# W520B.net
KiCad netlist of a schematic drawn in EAGLE
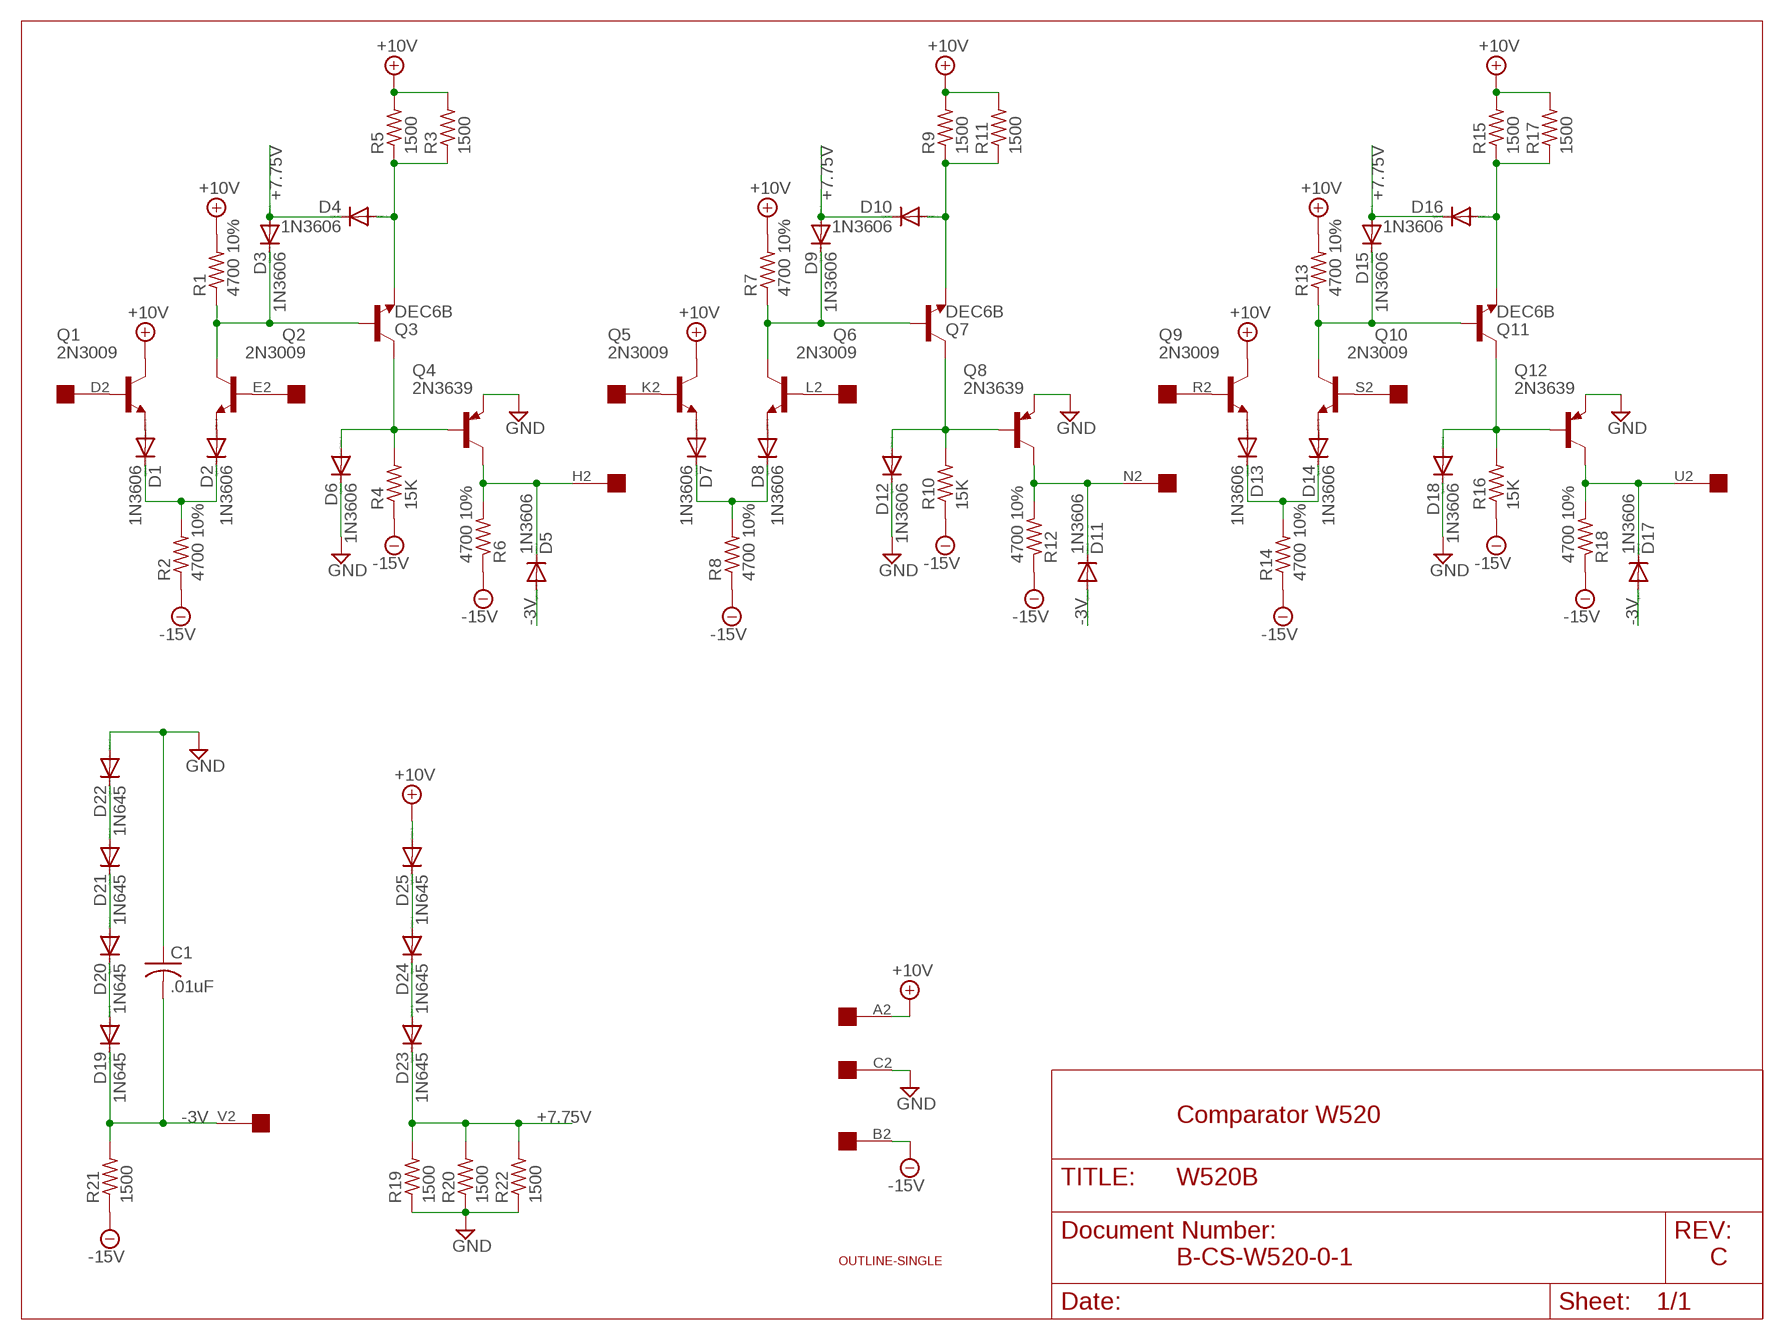
[diagram p0: schematic, sheet 1]

(export (version "E")
  (design (tool "Eeschema 10.0.6"))
  (components
    (comp (ref "C1")
      (value ".01uF")
      (footprint "eagle-import:C150-054X183")
      (libsource (lib "eagle-import") (part "C-US150-054X183"))
    )
    (comp (ref "D1")
      (value "1N3606")
      (footprint "eagle-import:DO35-10")
      (libsource (lib "eagle-import") (part "1N4148DO35-10"))
    )
    (comp (ref "D2")
      (value "1N3606")
      (footprint "eagle-import:DO35-10")
      (libsource (lib "eagle-import") (part "1N4148DO35-10"))
    )
    (comp (ref "D3")
      (value "1N3606")
      (footprint "eagle-import:DO35-10")
      (libsource (lib "eagle-import") (part "1N4148DO35-10"))
    )
    (comp (ref "D4")
      (value "1N3606")
      (footprint "eagle-import:DO35-10")
      (libsource (lib "eagle-import") (part "1N4148DO35-10"))
    )
    (comp (ref "D5")
      (value "1N3606")
      (footprint "eagle-import:DO35-10")
      (libsource (lib "eagle-import") (part "1N4148DO35-10"))
    )
    (comp (ref "D6")
      (value "1N3606")
      (footprint "eagle-import:DO35-10")
      (libsource (lib "eagle-import") (part "1N4148DO35-10"))
    )
    (comp (ref "D7")
      (value "1N3606")
      (footprint "eagle-import:DO35-10")
      (libsource (lib "eagle-import") (part "1N4148DO35-10"))
    )
    (comp (ref "D8")
      (value "1N3606")
      (footprint "eagle-import:DO35-10")
      (libsource (lib "eagle-import") (part "1N4148DO35-10"))
    )
    (comp (ref "D9")
      (value "1N3606")
      (footprint "eagle-import:DO35-10")
      (libsource (lib "eagle-import") (part "1N4148DO35-10"))
    )
    (comp (ref "D10")
      (value "1N3606")
      (footprint "eagle-import:DO35-10")
      (libsource (lib "eagle-import") (part "1N4148DO35-10"))
    )
    (comp (ref "D11")
      (value "1N3606")
      (footprint "eagle-import:DO35-10")
      (libsource (lib "eagle-import") (part "1N4148DO35-10"))
    )
    (comp (ref "D12")
      (value "1N3606")
      (footprint "eagle-import:DO35-10")
      (libsource (lib "eagle-import") (part "1N4148DO35-10"))
    )
    (comp (ref "D13")
      (value "1N3606")
      (footprint "eagle-import:DO35-10")
      (libsource (lib "eagle-import") (part "1N4148DO35-10"))
    )
    (comp (ref "D14")
      (value "1N3606")
      (footprint "eagle-import:DO35-10")
      (libsource (lib "eagle-import") (part "1N4148DO35-10"))
    )
    (comp (ref "D15")
      (value "1N3606")
      (footprint "eagle-import:DO35-10")
      (libsource (lib "eagle-import") (part "1N4148DO35-10"))
    )
    (comp (ref "D16")
      (value "1N3606")
      (footprint "eagle-import:DO35-10")
      (libsource (lib "eagle-import") (part "1N4148DO35-10"))
    )
    (comp (ref "D17")
      (value "1N3606")
      (footprint "eagle-import:DO35-10")
      (libsource (lib "eagle-import") (part "1N4148DO35-10"))
    )
    (comp (ref "D18")
      (value "1N3606")
      (footprint "eagle-import:DO35-10")
      (libsource (lib "eagle-import") (part "1N4148DO35-10"))
    )
    (comp (ref "D19")
      (value "1N645")
      (footprint "eagle-import:DO35-10")
      (libsource (lib "eagle-import") (part "1N4148DO35-10"))
    )
    (comp (ref "D20")
      (value "1N645")
      (footprint "eagle-import:DO35-10")
      (libsource (lib "eagle-import") (part "1N4148DO35-10"))
    )
    (comp (ref "D21")
      (value "1N645")
      (footprint "eagle-import:DO35-10")
      (libsource (lib "eagle-import") (part "1N4148DO35-10"))
    )
    (comp (ref "D22")
      (value "1N645")
      (footprint "eagle-import:DO35-10")
      (libsource (lib "eagle-import") (part "1N4148DO35-10"))
    )
    (comp (ref "D23")
      (value "1N645")
      (footprint "eagle-import:DO35-10")
      (libsource (lib "eagle-import") (part "1N4148DO35-10"))
    )
    (comp (ref "D24")
      (value "1N645")
      (footprint "eagle-import:DO35-10")
      (libsource (lib "eagle-import") (part "1N4148DO35-10"))
    )
    (comp (ref "D25")
      (value "1N645")
      (footprint "eagle-import:DO35-10")
      (libsource (lib "eagle-import") (part "1N4148DO35-10"))
    )
    (comp (ref "Q1")
      (value "2N3009")
      (footprint "eagle-import:TO5")
      (libsource (lib "eagle-import") (part "2N2102"))
    )
    (comp (ref "Q2")
      (value "2N3009")
      (footprint "eagle-import:TO5")
      (libsource (lib "eagle-import") (part "2N2102"))
    )
    (comp (ref "Q3")
      (value "DEC6B")
      (footprint "eagle-import:TO5")
      (libsource (lib "eagle-import") (part "2N2102"))
    )
    (comp (ref "Q4")
      (value "2N3639")
      (footprint "eagle-import:TO39")
      (libsource (lib "eagle-import") (part "2N2904"))
    )
    (comp (ref "Q5")
      (value "2N3009")
      (footprint "eagle-import:TO5")
      (libsource (lib "eagle-import") (part "2N2102"))
    )
    (comp (ref "Q6")
      (value "2N3009")
      (footprint "eagle-import:TO5")
      (libsource (lib "eagle-import") (part "2N2102"))
    )
    (comp (ref "Q7")
      (value "DEC6B")
      (footprint "eagle-import:TO5")
      (libsource (lib "eagle-import") (part "2N2102"))
    )
    (comp (ref "Q8")
      (value "2N3639")
      (footprint "eagle-import:TO39")
      (libsource (lib "eagle-import") (part "2N2904"))
    )
    (comp (ref "Q9")
      (value "2N3009")
      (footprint "eagle-import:TO5")
      (libsource (lib "eagle-import") (part "2N2102"))
    )
    (comp (ref "Q10")
      (value "2N3009")
      (footprint "eagle-import:TO5")
      (libsource (lib "eagle-import") (part "2N2102"))
    )
    (comp (ref "Q11")
      (value "DEC6B")
      (footprint "eagle-import:TO5")
      (libsource (lib "eagle-import") (part "2N2102"))
    )
    (comp (ref "Q12")
      (value "2N3639")
      (footprint "eagle-import:TO39")
      (libsource (lib "eagle-import") (part "2N2904"))
    )
    (comp (ref "R1")
      (value "4700 10%")
      (footprint "eagle-import:0207_10")
      (libsource (lib "eagle-import") (part "R-US_0207/10"))
    )
    (comp (ref "R2")
      (value "4700 10%")
      (footprint "eagle-import:0207_10")
      (libsource (lib "eagle-import") (part "R-US_0207/10"))
    )
    (comp (ref "R3")
      (value "1500")
      (footprint "eagle-import:0207_10")
      (libsource (lib "eagle-import") (part "R-US_0207/10"))
    )
    (comp (ref "R4")
      (value "15K")
      (footprint "eagle-import:0207_10")
      (libsource (lib "eagle-import") (part "R-US_0207/10"))
    )
    (comp (ref "R5")
      (value "1500")
      (footprint "eagle-import:0207_10")
      (libsource (lib "eagle-import") (part "R-US_0207/10"))
    )
    (comp (ref "R6")
      (value "4700 10%")
      (footprint "eagle-import:0207_10")
      (libsource (lib "eagle-import") (part "R-US_0207/10"))
    )
    (comp (ref "R7")
      (value "4700 10%")
      (footprint "eagle-import:0207_10")
      (libsource (lib "eagle-import") (part "R-US_0207/10"))
    )
    (comp (ref "R8")
      (value "4700 10%")
      (footprint "eagle-import:0207_10")
      (libsource (lib "eagle-import") (part "R-US_0207/10"))
    )
    (comp (ref "R9")
      (value "1500")
      (footprint "eagle-import:0207_10")
      (libsource (lib "eagle-import") (part "R-US_0207/10"))
    )
    (comp (ref "R10")
      (value "15K")
      (footprint "eagle-import:0207_10")
      (libsource (lib "eagle-import") (part "R-US_0207/10"))
    )
    (comp (ref "R11")
      (value "1500")
      (footprint "eagle-import:0207_10")
      (libsource (lib "eagle-import") (part "R-US_0207/10"))
    )
    (comp (ref "R12")
      (value "4700 10%")
      (footprint "eagle-import:0207_10")
      (libsource (lib "eagle-import") (part "R-US_0207/10"))
    )
    (comp (ref "R13")
      (value "4700 10%")
      (footprint "eagle-import:0207_10")
      (libsource (lib "eagle-import") (part "R-US_0207/10"))
    )
    (comp (ref "R14")
      (value "4700 10%")
      (footprint "eagle-import:0207_10")
      (libsource (lib "eagle-import") (part "R-US_0207/10"))
    )
    (comp (ref "R15")
      (value "1500")
      (footprint "eagle-import:0207_10")
      (libsource (lib "eagle-import") (part "R-US_0207/10"))
    )
    (comp (ref "R16")
      (value "15K")
      (footprint "eagle-import:0207_10")
      (libsource (lib "eagle-import") (part "R-US_0207/10"))
    )
    (comp (ref "R17")
      (value "1500")
      (footprint "eagle-import:0207_10")
      (libsource (lib "eagle-import") (part "R-US_0207/10"))
    )
    (comp (ref "R18")
      (value "4700 10%")
      (footprint "eagle-import:0207_10")
      (libsource (lib "eagle-import") (part "R-US_0207/10"))
    )
    (comp (ref "R19")
      (value "1500")
      (footprint "eagle-import:0207_10")
      (libsource (lib "eagle-import") (part "R-US_0207/10"))
    )
    (comp (ref "R20")
      (value "1500")
      (footprint "eagle-import:0207_10")
      (libsource (lib "eagle-import") (part "R-US_0207/10"))
    )
    (comp (ref "R21")
      (value "1500")
      (footprint "eagle-import:0207_10")
      (libsource (lib "eagle-import") (part "R-US_0207/10"))
    )
    (comp (ref "R22")
      (value "1500")
      (footprint "eagle-import:0207_10")
      (libsource (lib "eagle-import") (part "R-US_0207/10"))
    )
    (comp (ref "U$1")
      (value "OUTLINE-SINGLE")
      (footprint "eagle-import:SINGLE")
      (libsource (lib "eagle-import") (part "OUTLINE-SINGLE"))
    )
    (comp (ref "U$2")
      (value "EDGE-1")
      (footprint "eagle-import:EDGE-CON1")
      (libsource (lib "eagle-import") (part "EDGE-1"))
    )
  )
  (nets
    (net (code "1") (name "+10V") (class "Default")
      (node (ref "D25") (pin "A") (pinfunction "A_A") (pintype "passive"))
      (node (ref "Q1") (pin "3") (pinfunction "C_3") (pintype "passive"))
      (node (ref "Q5") (pin "3") (pinfunction "C_3") (pintype "passive"))
      (node (ref "Q9") (pin "3") (pinfunction "C_3") (pintype "passive"))
      (node (ref "R1") (pin "2") (pinfunction "2_2") (pintype "passive"))
      (node (ref "R11") (pin "2") (pinfunction "2_2") (pintype "passive"))
      (node (ref "R13") (pin "2") (pinfunction "2_2") (pintype "passive"))
      (node (ref "R15") (pin "2") (pinfunction "2_2") (pintype "passive"))
      (node (ref "R17") (pin "2") (pinfunction "2_2") (pintype "passive"))
      (node (ref "R3") (pin "2") (pinfunction "2_2") (pintype "passive"))
      (node (ref "R5") (pin "2") (pinfunction "2_2") (pintype "passive"))
      (node (ref "R7") (pin "2") (pinfunction "2_2") (pintype "passive"))
      (node (ref "R9") (pin "2") (pinfunction "2_2") (pintype "passive"))
      (node (ref "U$2") (pin "A2") (pinfunction "1_A2") (pintype "bidirectional"))
    )
    (net (code "2") (name "-15V") (class "Default")
      (node (ref "R10") (pin "1") (pinfunction "1_1") (pintype "passive"))
      (node (ref "R12") (pin "1") (pinfunction "1_1") (pintype "passive"))
      (node (ref "R14") (pin "1") (pinfunction "1_1") (pintype "passive"))
      (node (ref "R16") (pin "1") (pinfunction "1_1") (pintype "passive"))
      (node (ref "R18") (pin "1") (pinfunction "1_1") (pintype "passive"))
      (node (ref "R2") (pin "1") (pinfunction "1_1") (pintype "passive"))
      (node (ref "R21") (pin "1") (pinfunction "1_1") (pintype "passive"))
      (node (ref "R4") (pin "1") (pinfunction "1_1") (pintype "passive"))
      (node (ref "R6") (pin "1") (pinfunction "1_1") (pintype "passive"))
      (node (ref "R8") (pin "1") (pinfunction "1_1") (pintype "passive"))
      (node (ref "U$2") (pin "B2") (pinfunction "1_B2") (pintype "bidirectional"))
    )
    (net (code "3") (name "/+7.75V") (class "Default")
      (node (ref "D10") (pin "C") (pinfunction "C_C") (pintype "passive"))
      (node (ref "D15") (pin "A") (pinfunction "A_A") (pintype "passive"))
      (node (ref "D16") (pin "C") (pinfunction "C_C") (pintype "passive"))
      (node (ref "D23") (pin "C") (pinfunction "C_C") (pintype "passive"))
      (node (ref "D3") (pin "A") (pinfunction "A_A") (pintype "passive"))
      (node (ref "D4") (pin "C") (pinfunction "C_C") (pintype "passive"))
      (node (ref "D9") (pin "A") (pinfunction "A_A") (pintype "passive"))
      (node (ref "R19") (pin "2") (pinfunction "2_2") (pintype "passive"))
      (node (ref "R20") (pin "2") (pinfunction "2_2") (pintype "passive"))
      (node (ref "R22") (pin "2") (pinfunction "2_2") (pintype "passive"))
    )
    (net (code "4") (name "/-3V") (class "Default")
      (node (ref "C1") (pin "2") (pinfunction "2_2") (pintype "passive"))
      (node (ref "D11") (pin "A") (pinfunction "A_A") (pintype "passive"))
      (node (ref "D17") (pin "A") (pinfunction "A_A") (pintype "passive"))
      (node (ref "D19") (pin "C") (pinfunction "C_C") (pintype "passive"))
      (node (ref "D5") (pin "A") (pinfunction "A_A") (pintype "passive"))
      (node (ref "R21") (pin "2") (pinfunction "2_2") (pintype "passive"))
      (node (ref "U$2") (pin "V2") (pinfunction "1_V2") (pintype "bidirectional"))
    )
    (net (code "5") (name "GND") (class "Default")
      (node (ref "C1") (pin "1") (pinfunction "1_1") (pintype "passive"))
      (node (ref "D12") (pin "C") (pinfunction "C_C") (pintype "passive"))
      (node (ref "D18") (pin "C") (pinfunction "C_C") (pintype "passive"))
      (node (ref "D22") (pin "A") (pinfunction "A_A") (pintype "passive"))
      (node (ref "D6") (pin "C") (pinfunction "C_C") (pintype "passive"))
      (node (ref "Q12") (pin "1") (pinfunction "E_1") (pintype "passive"))
      (node (ref "Q4") (pin "1") (pinfunction "E_1") (pintype "passive"))
      (node (ref "Q8") (pin "1") (pinfunction "E_1") (pintype "passive"))
      (node (ref "R19") (pin "1") (pinfunction "1_1") (pintype "passive"))
      (node (ref "R20") (pin "1") (pinfunction "1_1") (pintype "passive"))
      (node (ref "R22") (pin "1") (pinfunction "1_1") (pintype "passive"))
      (node (ref "U$2") (pin "C2") (pinfunction "1_C2") (pintype "bidirectional"))
    )
    (net (code "6") (name "Net-(D1-PadC)") (class "Default")
      (node (ref "D1") (pin "C") (pinfunction "C_C") (pintype "passive"))
      (node (ref "D2") (pin "C") (pinfunction "C_C") (pintype "passive"))
      (node (ref "R2") (pin "2") (pinfunction "2_2") (pintype "passive"))
    )
    (net (code "7") (name "Net-(D7-PadC)") (class "Default")
      (node (ref "D7") (pin "C") (pinfunction "C_C") (pintype "passive"))
      (node (ref "D8") (pin "C") (pinfunction "C_C") (pintype "passive"))
      (node (ref "R8") (pin "2") (pinfunction "2_2") (pintype "passive"))
    )
    (net (code "8") (name "Net-(D13-PadC)") (class "Default")
      (node (ref "D13") (pin "C") (pinfunction "C_C") (pintype "passive"))
      (node (ref "D14") (pin "C") (pinfunction "C_C") (pintype "passive"))
      (node (ref "R14") (pin "2") (pinfunction "2_2") (pintype "passive"))
    )
    (net (code "9") (name "Net-(D19-PadA)") (class "Default")
      (node (ref "D19") (pin "A") (pinfunction "A_A") (pintype "passive"))
      (node (ref "D20") (pin "C") (pinfunction "C_C") (pintype "passive"))
    )
    (net (code "10") (name "Net-(D20-PadA)") (class "Default")
      (node (ref "D20") (pin "A") (pinfunction "A_A") (pintype "passive"))
      (node (ref "D21") (pin "C") (pinfunction "C_C") (pintype "passive"))
    )
    (net (code "11") (name "Net-(D21-PadA)") (class "Default")
      (node (ref "D21") (pin "A") (pinfunction "A_A") (pintype "passive"))
      (node (ref "D22") (pin "C") (pinfunction "C_C") (pintype "passive"))
    )
    (net (code "12") (name "Net-(D23-PadA)") (class "Default")
      (node (ref "D23") (pin "A") (pinfunction "A_A") (pintype "passive"))
      (node (ref "D24") (pin "C") (pinfunction "C_C") (pintype "passive"))
    )
    (net (code "13") (name "Net-(D24-PadA)") (class "Default")
      (node (ref "D24") (pin "A") (pinfunction "A_A") (pintype "passive"))
      (node (ref "D25") (pin "C") (pinfunction "C_C") (pintype "passive"))
    )
    (net (code "14") (name "Net-(Q1-B)") (class "Default")
      (node (ref "Q1") (pin "2") (pinfunction "B_2") (pintype "passive"))
      (node (ref "U$2") (pin "D2") (pinfunction "1_D2") (pintype "bidirectional"))
    )
    (net (code "15") (name "Net-(Q1-E)") (class "Default")
      (node (ref "D1") (pin "A") (pinfunction "A_A") (pintype "passive"))
      (node (ref "Q1") (pin "1") (pinfunction "E_1") (pintype "passive"))
    )
    (net (code "16") (name "Net-(Q2-B)") (class "Default")
      (node (ref "Q2") (pin "2") (pinfunction "B_2") (pintype "passive"))
      (node (ref "U$2") (pin "E2") (pinfunction "1_E2") (pintype "bidirectional"))
    )
    (net (code "17") (name "Net-(Q2-C)") (class "Default")
      (node (ref "D3") (pin "C") (pinfunction "C_C") (pintype "passive"))
      (node (ref "Q2") (pin "3") (pinfunction "C_3") (pintype "passive"))
      (node (ref "Q3") (pin "2") (pinfunction "B_2") (pintype "passive"))
      (node (ref "R1") (pin "1") (pinfunction "1_1") (pintype "passive"))
    )
    (net (code "18") (name "Net-(Q2-E)") (class "Default")
      (node (ref "D2") (pin "A") (pinfunction "A_A") (pintype "passive"))
      (node (ref "Q2") (pin "1") (pinfunction "E_1") (pintype "passive"))
    )
    (net (code "19") (name "Net-(Q3-C)") (class "Default")
      (node (ref "D6") (pin "A") (pinfunction "A_A") (pintype "passive"))
      (node (ref "Q3") (pin "3") (pinfunction "C_3") (pintype "passive"))
      (node (ref "Q4") (pin "2") (pinfunction "B_2") (pintype "passive"))
      (node (ref "R4") (pin "2") (pinfunction "2_2") (pintype "passive"))
    )
    (net (code "20") (name "Net-(Q3-E)") (class "Default")
      (node (ref "D4") (pin "A") (pinfunction "A_A") (pintype "passive"))
      (node (ref "Q3") (pin "1") (pinfunction "E_1") (pintype "passive"))
      (node (ref "R3") (pin "1") (pinfunction "1_1") (pintype "passive"))
      (node (ref "R5") (pin "1") (pinfunction "1_1") (pintype "passive"))
    )
    (net (code "21") (name "Net-(Q4-C)") (class "Default")
      (node (ref "D5") (pin "C") (pinfunction "C_C") (pintype "passive"))
      (node (ref "Q4") (pin "3") (pinfunction "C_3") (pintype "passive"))
      (node (ref "R6") (pin "2") (pinfunction "2_2") (pintype "passive"))
      (node (ref "U$2") (pin "H2") (pinfunction "1_H2") (pintype "bidirectional"))
    )
    (net (code "22") (name "Net-(Q5-B)") (class "Default")
      (node (ref "Q5") (pin "2") (pinfunction "B_2") (pintype "passive"))
      (node (ref "U$2") (pin "K2") (pinfunction "1_K2") (pintype "bidirectional"))
    )
    (net (code "23") (name "Net-(Q5-E)") (class "Default")
      (node (ref "D7") (pin "A") (pinfunction "A_A") (pintype "passive"))
      (node (ref "Q5") (pin "1") (pinfunction "E_1") (pintype "passive"))
    )
    (net (code "24") (name "Net-(Q6-B)") (class "Default")
      (node (ref "Q6") (pin "2") (pinfunction "B_2") (pintype "passive"))
      (node (ref "U$2") (pin "L2") (pinfunction "1_L2") (pintype "bidirectional"))
    )
    (net (code "25") (name "Net-(Q6-C)") (class "Default")
      (node (ref "D9") (pin "C") (pinfunction "C_C") (pintype "passive"))
      (node (ref "Q6") (pin "3") (pinfunction "C_3") (pintype "passive"))
      (node (ref "Q7") (pin "2") (pinfunction "B_2") (pintype "passive"))
      (node (ref "R7") (pin "1") (pinfunction "1_1") (pintype "passive"))
    )
    (net (code "26") (name "Net-(Q6-E)") (class "Default")
      (node (ref "D8") (pin "A") (pinfunction "A_A") (pintype "passive"))
      (node (ref "Q6") (pin "1") (pinfunction "E_1") (pintype "passive"))
    )
    (net (code "27") (name "Net-(Q7-C)") (class "Default")
      (node (ref "D12") (pin "A") (pinfunction "A_A") (pintype "passive"))
      (node (ref "Q7") (pin "3") (pinfunction "C_3") (pintype "passive"))
      (node (ref "Q8") (pin "2") (pinfunction "B_2") (pintype "passive"))
      (node (ref "R10") (pin "2") (pinfunction "2_2") (pintype "passive"))
    )
    (net (code "28") (name "Net-(Q7-E)") (class "Default")
      (node (ref "D10") (pin "A") (pinfunction "A_A") (pintype "passive"))
      (node (ref "Q7") (pin "1") (pinfunction "E_1") (pintype "passive"))
      (node (ref "R11") (pin "1") (pinfunction "1_1") (pintype "passive"))
      (node (ref "R9") (pin "1") (pinfunction "1_1") (pintype "passive"))
    )
    (net (code "29") (name "Net-(Q8-C)") (class "Default")
      (node (ref "D11") (pin "C") (pinfunction "C_C") (pintype "passive"))
      (node (ref "Q8") (pin "3") (pinfunction "C_3") (pintype "passive"))
      (node (ref "R12") (pin "2") (pinfunction "2_2") (pintype "passive"))
      (node (ref "U$2") (pin "N2") (pinfunction "1_N2") (pintype "bidirectional"))
    )
    (net (code "30") (name "Net-(Q9-B)") (class "Default")
      (node (ref "Q9") (pin "2") (pinfunction "B_2") (pintype "passive"))
      (node (ref "U$2") (pin "R2") (pinfunction "1_R2") (pintype "bidirectional"))
    )
    (net (code "31") (name "Net-(Q9-E)") (class "Default")
      (node (ref "D13") (pin "A") (pinfunction "A_A") (pintype "passive"))
      (node (ref "Q9") (pin "1") (pinfunction "E_1") (pintype "passive"))
    )
    (net (code "32") (name "Net-(Q10-B)") (class "Default")
      (node (ref "Q10") (pin "2") (pinfunction "B_2") (pintype "passive"))
      (node (ref "U$2") (pin "S2") (pinfunction "1_S2") (pintype "bidirectional"))
    )
    (net (code "33") (name "Net-(Q10-C)") (class "Default")
      (node (ref "D15") (pin "C") (pinfunction "C_C") (pintype "passive"))
      (node (ref "Q10") (pin "3") (pinfunction "C_3") (pintype "passive"))
      (node (ref "Q11") (pin "2") (pinfunction "B_2") (pintype "passive"))
      (node (ref "R13") (pin "1") (pinfunction "1_1") (pintype "passive"))
    )
    (net (code "34") (name "Net-(Q10-E)") (class "Default")
      (node (ref "D14") (pin "A") (pinfunction "A_A") (pintype "passive"))
      (node (ref "Q10") (pin "1") (pinfunction "E_1") (pintype "passive"))
    )
    (net (code "35") (name "Net-(Q11-C)") (class "Default")
      (node (ref "D18") (pin "A") (pinfunction "A_A") (pintype "passive"))
      (node (ref "Q11") (pin "3") (pinfunction "C_3") (pintype "passive"))
      (node (ref "Q12") (pin "2") (pinfunction "B_2") (pintype "passive"))
      (node (ref "R16") (pin "2") (pinfunction "2_2") (pintype "passive"))
    )
    (net (code "36") (name "Net-(Q11-E)") (class "Default")
      (node (ref "D16") (pin "A") (pinfunction "A_A") (pintype "passive"))
      (node (ref "Q11") (pin "1") (pinfunction "E_1") (pintype "passive"))
      (node (ref "R15") (pin "1") (pinfunction "1_1") (pintype "passive"))
      (node (ref "R17") (pin "1") (pinfunction "1_1") (pintype "passive"))
    )
    (net (code "37") (name "Net-(Q12-C)") (class "Default")
      (node (ref "D17") (pin "C") (pinfunction "C_C") (pintype "passive"))
      (node (ref "Q12") (pin "3") (pinfunction "C_3") (pintype "passive"))
      (node (ref "R18") (pin "2") (pinfunction "2_2") (pintype "passive"))
      (node (ref "U$2") (pin "U2") (pinfunction "1_U2") (pintype "bidirectional"))
    )
  )
)
